# motor_drv.net
KiCad netlist of a schematic drawn in Altium Designer
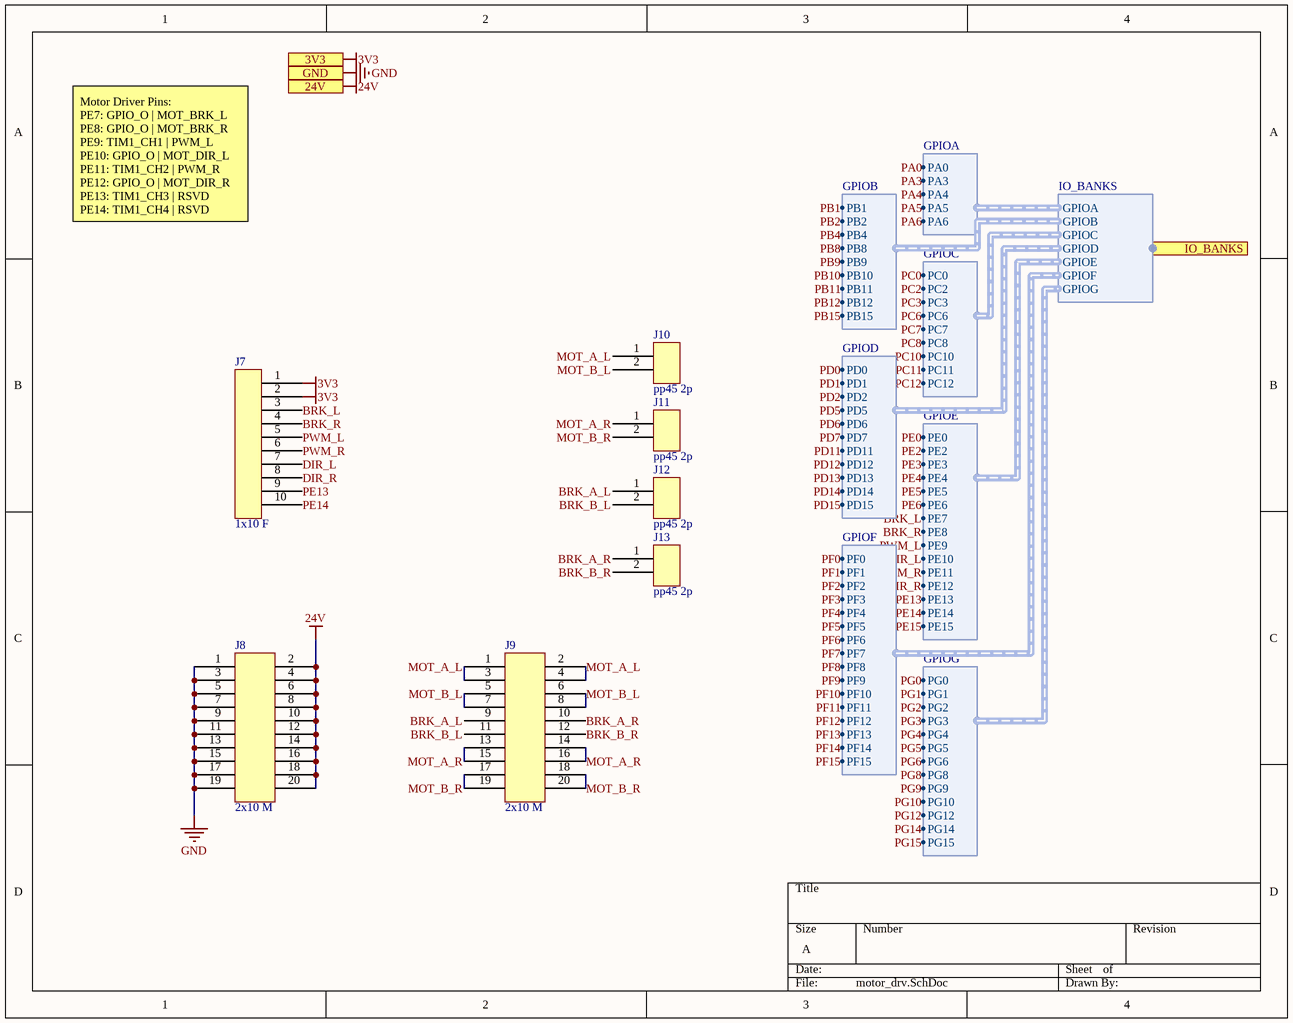
[diagram p0: motor_drv.SchDoc]

(export (version "E")
  (design (tool "Eeschema 10.0.6"))
  (components
    (comp (ref "J7")
      (value "1x10 F")
      (footprint "CONN HDR 1x10 F")
      (description "CONN header 1x10 F")
      (libsource (lib "streetbot") (part "CONN header 1x10 F"))
    )
    (comp (ref "J8")
      (value "2x10 M")
      (footprint "CONN HDR 2x10 M TOP")
      (description "SBH11-PBPC-D10-ST-BK")
      (libsource (lib "streetbot") (part "CONN Header 2x10 M"))
    )
    (comp (ref "J9")
      (value "2x10 M")
      (footprint "CONN HDR 2x10 M TOP")
      (description "SBH11-PBPC-D10-ST-BK")
      (libsource (lib "streetbot") (part "CONN Header 2x10 M"))
    )
    (comp (ref "J10")
      (value "pp45 2p")
      (footprint "CONN PP45 2P VERT")
      (description "Heavy Duty Power Connectors PCB45 VERT.MT.SHORT TAIL LP CONT")
      (libsource (lib "streetbot") (part "CONN pp45 1x2 vert"))
    )
    (comp (ref "J11")
      (value "pp45 2p")
      (footprint "CONN PP45 2P VERT")
      (description "Heavy Duty Power Connectors PCB45 VERT.MT.SHORT TAIL LP CONT")
      (libsource (lib "streetbot") (part "CONN pp45 1x2 vert"))
    )
    (comp (ref "J12")
      (value "pp45 2p")
      (footprint "CONN PP45 2P VERT")
      (description "Heavy Duty Power Connectors PCB45 VERT.MT.SHORT TAIL LP CONT")
      (libsource (lib "streetbot") (part "CONN pp45 1x2 vert"))
    )
    (comp (ref "J13")
      (value "pp45 2p")
      (footprint "CONN PP45 2P VERT")
      (description "Heavy Duty Power Connectors PCB45 VERT.MT.SHORT TAIL LP CONT")
      (libsource (lib "streetbot") (part "CONN pp45 1x2 vert"))
    )
  )
  (nets
    (net (code "8") (name "/BRK_A_L") (class "Default")
      (node (ref "J12") (pin "1") (pintype "passive"))
      (node (ref "J9") (pin "9") (pintype "passive"))
    )
    (net (code "9") (name "/BRK_A_R") (class "Default")
      (node (ref "J13") (pin "1") (pintype "passive"))
      (node (ref "J9") (pin "10") (pintype "passive"))
    )
    (net (code "10") (name "/BRK_B_L") (class "Default")
      (node (ref "J12") (pin "2") (pintype "passive"))
      (node (ref "J9") (pin "11") (pintype "passive"))
    )
    (net (code "11") (name "/BRK_B_R") (class "Default")
      (node (ref "J13") (pin "2") (pintype "passive"))
      (node (ref "J9") (pin "12") (pintype "passive"))
    )
    (net (code "12") (name "/BRK_L") (class "Default") (node (ref "J7") (pin "3") (pintype "passive")))
    (net (code "13") (name "/BRK_R") (class "Default") (node (ref "J7") (pin "4") (pintype "passive")))
    (net (code "14") (name "/DIR_L") (class "Default") (node (ref "J7") (pin "7") (pintype "passive")))
    (net (code "15") (name "/DIR_R") (class "Default") (node (ref "J7") (pin "8") (pintype "passive")))
    (net (code "17") (name "/MOT_A_L") (class "Default")
      (node (ref "J10") (pin "1") (pintype "passive"))
      (node (ref "J9") (pin "1") (pintype "passive"))
      (node (ref "J9") (pin "2") (pintype "passive"))
      (node (ref "J9") (pin "3") (pintype "passive"))
      (node (ref "J9") (pin "4") (pintype "passive"))
    )
    (net (code "18") (name "/MOT_A_R") (class "Default")
      (node (ref "J11") (pin "1") (pintype "passive"))
      (node (ref "J9") (pin "13") (pintype "passive"))
      (node (ref "J9") (pin "14") (pintype "passive"))
      (node (ref "J9") (pin "15") (pintype "passive"))
      (node (ref "J9") (pin "16") (pintype "passive"))
    )
    (net (code "19") (name "/MOT_B_L") (class "Default")
      (node (ref "J10") (pin "2") (pintype "passive"))
      (node (ref "J9") (pin "5") (pintype "passive"))
      (node (ref "J9") (pin "6") (pintype "passive"))
      (node (ref "J9") (pin "7") (pintype "passive"))
      (node (ref "J9") (pin "8") (pintype "passive"))
    )
    (net (code "20") (name "/MOT_B_R") (class "Default")
      (node (ref "J11") (pin "2") (pintype "passive"))
      (node (ref "J9") (pin "17") (pintype "passive"))
      (node (ref "J9") (pin "18") (pintype "passive"))
      (node (ref "J9") (pin "19") (pintype "passive"))
      (node (ref "J9") (pin "20") (pintype "passive"))
    )
    (net (code "61") (name "/PE13") (class "Default") (node (ref "J7") (pin "9") (pintype "passive")))
    (net (code "62") (name "/PE14") (class "Default") (node (ref "J7") (pin "10") (pintype "passive")))
    (net (code "93") (name "/PWM_L") (class "Default") (node (ref "J7") (pin "5") (pintype "passive")))
    (net (code "94") (name "/PWM_R") (class "Default") (node (ref "J7") (pin "6") (pintype "passive")))
    (net (code "101") (name "3V3") (class "Default")
      (node (ref "J7") (pin "1") (pintype "passive"))
      (node (ref "J7") (pin "2") (pintype "passive"))
    )
    (net (code "102") (name "24V") (class "Default")
      (node (ref "J8") (pin "10") (pintype "passive"))
      (node (ref "J8") (pin "12") (pintype "passive"))
      (node (ref "J8") (pin "14") (pintype "passive"))
      (node (ref "J8") (pin "16") (pintype "passive"))
      (node (ref "J8") (pin "18") (pintype "passive"))
      (node (ref "J8") (pin "2") (pintype "passive"))
      (node (ref "J8") (pin "20") (pintype "passive"))
      (node (ref "J8") (pin "4") (pintype "passive"))
      (node (ref "J8") (pin "6") (pintype "passive"))
      (node (ref "J8") (pin "8") (pintype "passive"))
    )
    (net (code "103") (name "GND") (class "Default")
      (node (ref "J8") (pin "1") (pintype "passive"))
      (node (ref "J8") (pin "11") (pintype "passive"))
      (node (ref "J8") (pin "13") (pintype "passive"))
      (node (ref "J8") (pin "15") (pintype "passive"))
      (node (ref "J8") (pin "17") (pintype "passive"))
      (node (ref "J8") (pin "19") (pintype "passive"))
      (node (ref "J8") (pin "3") (pintype "passive"))
      (node (ref "J8") (pin "5") (pintype "passive"))
      (node (ref "J8") (pin "7") (pintype "passive"))
      (node (ref "J8") (pin "9") (pintype "passive"))
    )
  )
)
